# WIFI_BLE.net
KiCad netlist of a schematic drawn in Altium Designer
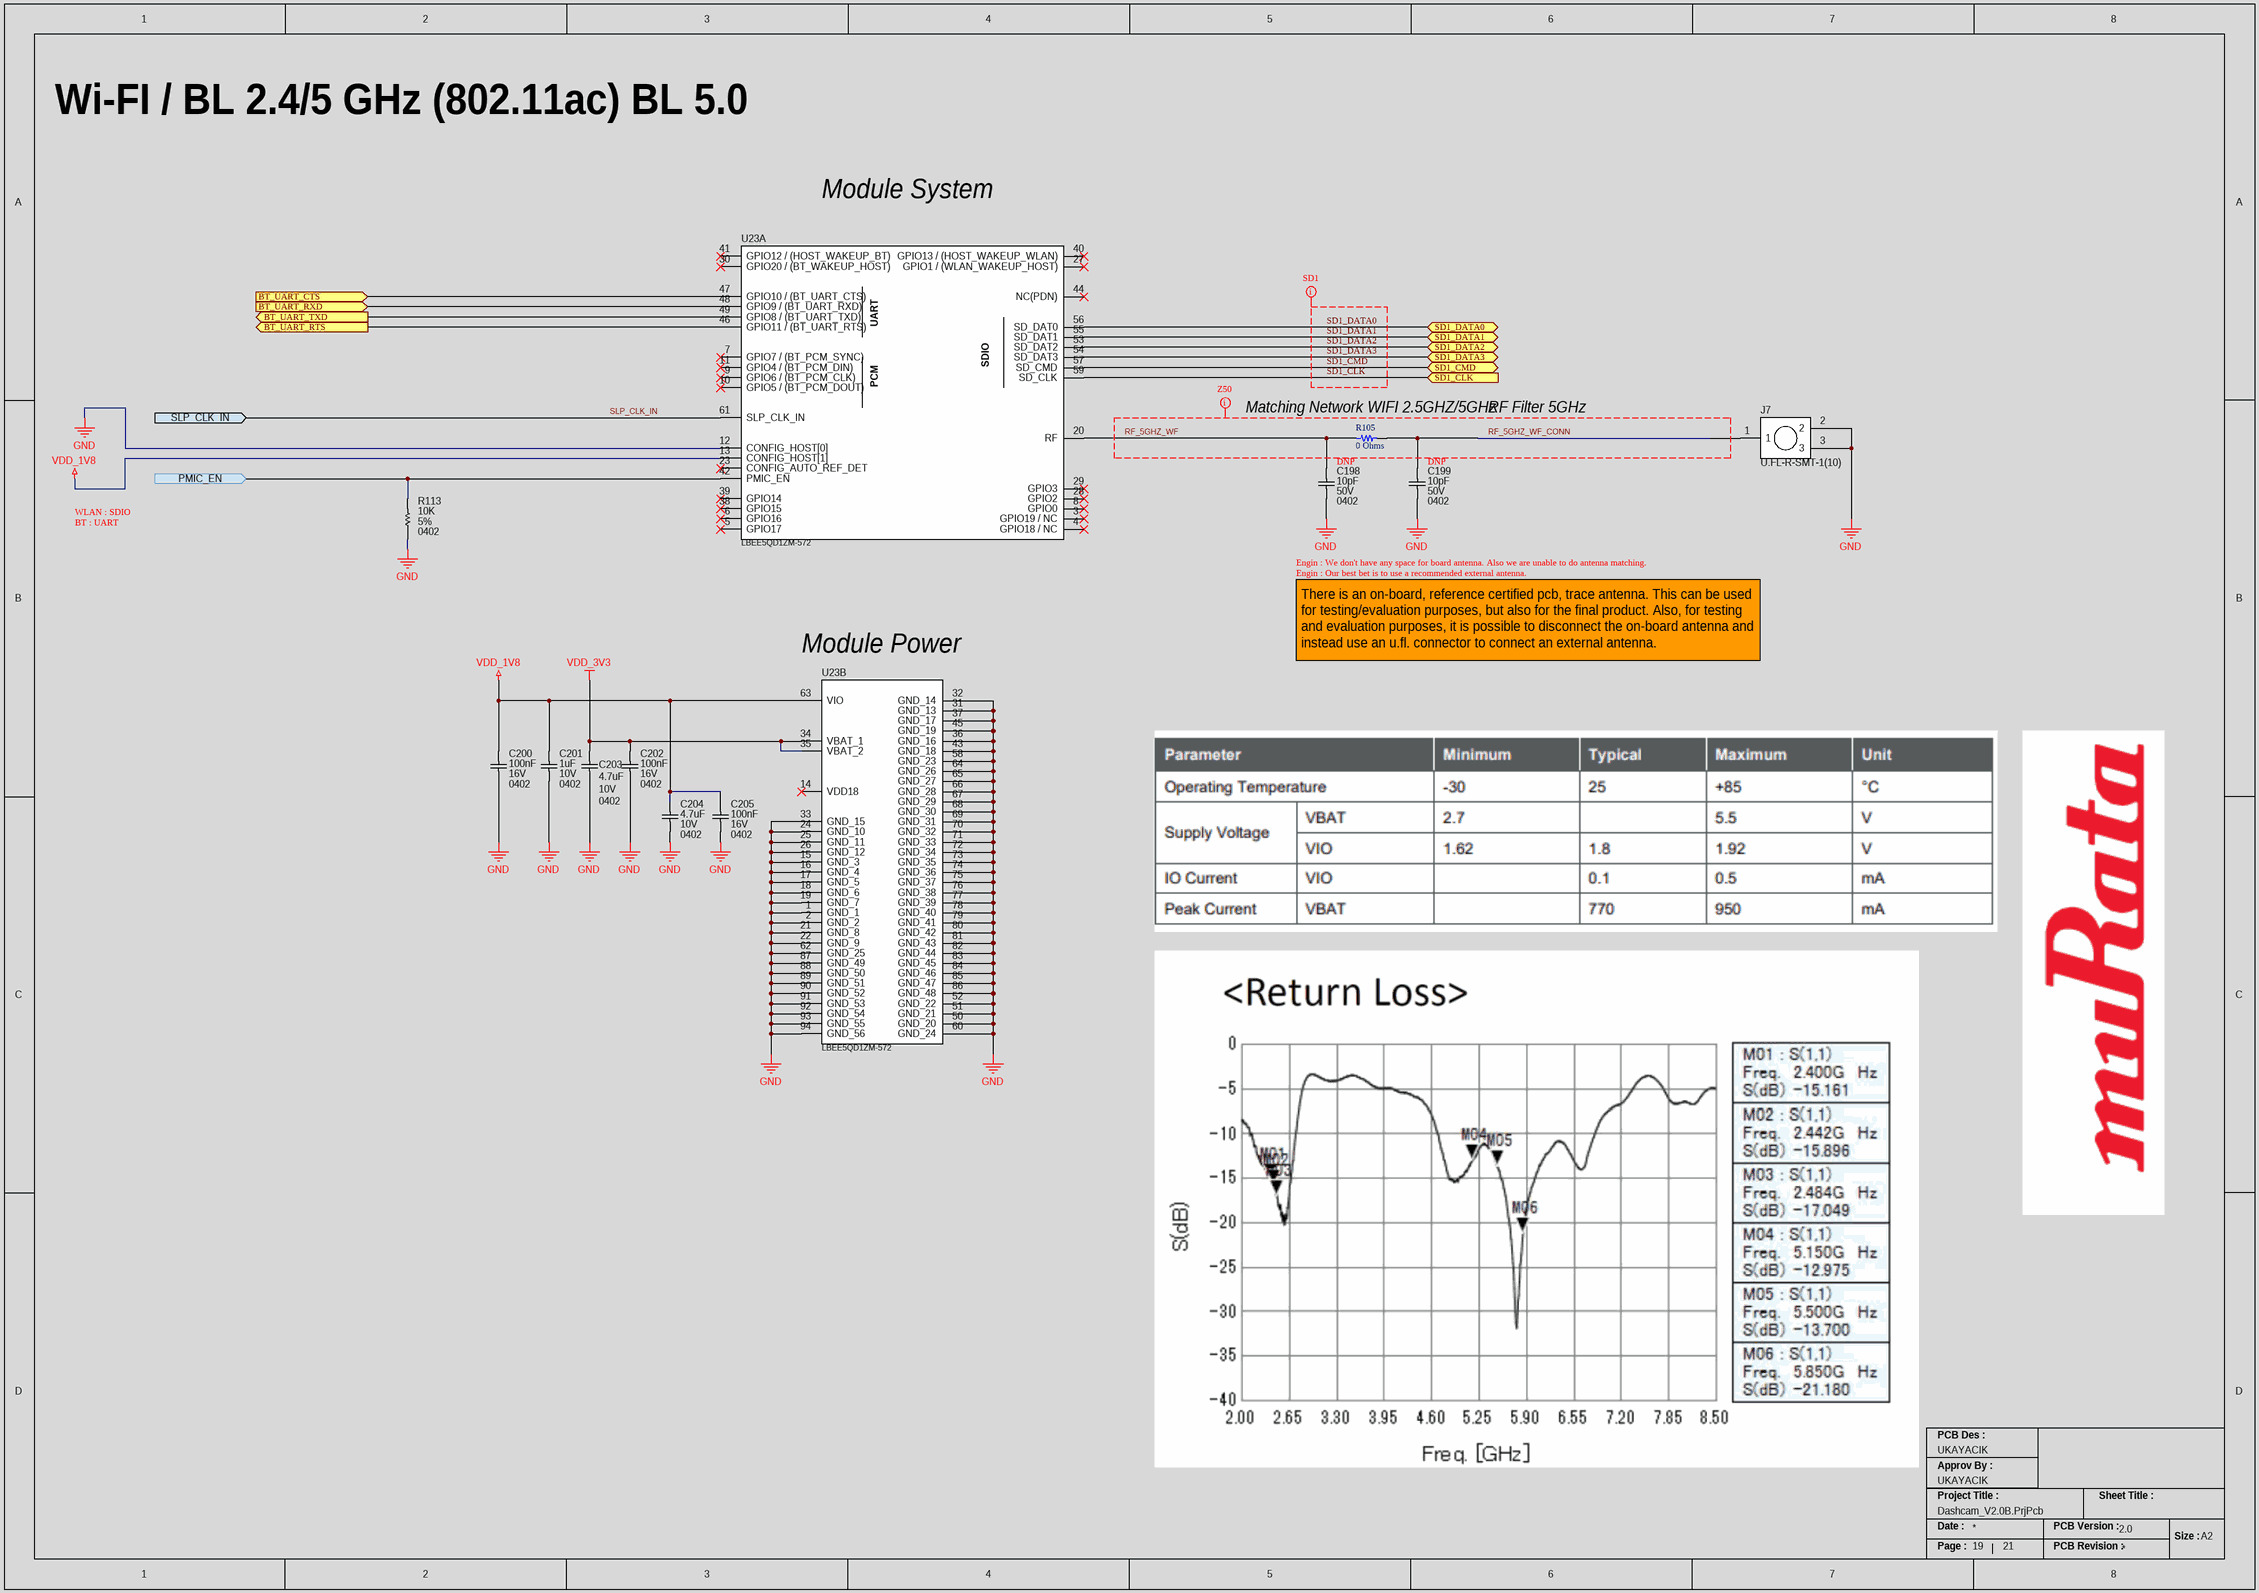
[diagram p0: WIFI_BLE.SchDoc]

(export (version "E")
  (design (tool "Eeschema 10.0.6"))
  (components
    (comp (ref "C198")
      (value "GJM1555C1H100FB01D")
      (footprint "CAP_0402_CAPC1005X05N")
      (description "Multilayer Ceramic Capacitor, 10 pF, 50 V, ± 1%, C0G (NP0), 0402 [1005 Metric]")
      (fields
        (field (name "MANUFACTURER") "Murata")
        (field (name "TOLERANCE") "1%")
        (field (name "CASE/PACKAGE") "0402")
        (field (name "VOLTAGE RATING") "50V")
        (field (name "CAPACITANCE") "10pF")
      )
      (libsource (lib "Electronic Devices_LIB") (part "CAP_10PF_50V_NP0_0402"))
    )
    (comp (ref "C199")
      (value "GJM1555C1H100FB01D")
      (footprint "CAP_0402_CAPC1005X05N")
      (description "Multilayer Ceramic Capacitor, 10 pF, 50 V, ± 1%, C0G (NP0), 0402 [1005 Metric]")
      (fields
        (field (name "MANUFACTURER") "Murata")
        (field (name "TOLERANCE") "1%")
        (field (name "CASE/PACKAGE") "0402")
        (field (name "VOLTAGE RATING") "50V")
        (field (name "CAPACITANCE") "10pF")
      )
      (libsource (lib "Electronic Devices_LIB") (part "CAP_10PF_50V_NP0_0402"))
    )
    (comp (ref "C200")
      (value "CL05B104KO5NNNC")
      (footprint "CAP_0402_CAPC1005X05N")
      (description "Multilayer Ceramic Capacitor, 0.1 uF, 16 V, ± 10%, X7R, 0402 [1005 Metric]")
      (fields
        (field (name "MANUFACTURER") "Samsung")
        (field (name "TOLERANCE") "10%")
        (field (name "VOLTAGE RATING") "16V")
        (field (name "CAPACITANCE") "100nF")
        (field (name "CASE/PACKAGE") "0402")
      )
      (libsource (lib "Electronic Devices_LIB") (part "CAP_100NF_16V_X7R_0402"))
    )
    (comp (ref "C201")
      (value "GRM155C81A105KA12D")
      (footprint "CAP_0402_CAPC1005X05N")
      (description "0402 10 V 1 uF ±10% Tolerance X6S Multilayer Ceramic Capacitor")
      (fields
        (field (name "MANUFACTURER") "Murata")
        (field (name "TOLERANCE") "10%")
        (field (name "VOLTAGE RATING") "10V")
        (field (name "CAPACITANCE") "1uF")
        (field (name "CASE/PACKAGE") "0402")
      )
      (libsource (lib "Electronic Devices_LIB") (part "CAP_1UF_10V_X6S_0402"))
    )
    (comp (ref "C202")
      (value "CL05B104KO5NNNC")
      (footprint "CAP_0402_CAPC1005X05N")
      (description "Multilayer Ceramic Capacitor, 0.1 uF, 16 V, ± 10%, X7R, 0402 [1005 Metric]")
      (fields
        (field (name "MANUFACTURER") "Samsung")
        (field (name "TOLERANCE") "10%")
        (field (name "VOLTAGE RATING") "16V")
        (field (name "CAPACITANCE") "100nF")
        (field (name "CASE/PACKAGE") "0402")
      )
      (libsource (lib "Electronic Devices_LIB") (part "CAP_100NF_16V_X7R_0402"))
    )
    (comp (ref "C203")
      (value "CL05A475KP5NRNC")
      (footprint "CAP_0402_CAPC1005X05N")
      (description "Multilayer Ceramic Capacitor, 4.7 uF, 10 V, ± 10%, X5R, 0402 [1005 Metric]")
      (fields
        (field (name "MANUFACTURER") "Samsung")
        (field (name "TOLERANCE") "10%")
        (field (name "CAPACITANCE") "4.7uF")
        (field (name "VOLTAGE RATING") "10V")
        (field (name "CASE/PACKAGE") "0402")
      )
      (libsource (lib "Electronic Devices_LIB") (part "CAP_4.7UF_10V_X5R_0402"))
    )
    (comp (ref "C204")
      (value "CL05A475KP5NRNC")
      (footprint "CAP_0402_CAPC1005X05N")
      (description "Multilayer Ceramic Capacitor, 4.7 uF, 10 V, ± 10%, X5R, 0402 [1005 Metric]")
      (fields
        (field (name "MANUFACTURER") "Samsung")
        (field (name "TOLERANCE") "10%")
        (field (name "CAPACITANCE") "4.7uF")
        (field (name "VOLTAGE RATING") "10V")
        (field (name "CASE/PACKAGE") "0402")
      )
      (libsource (lib "Electronic Devices_LIB") (part "CAP_4.7UF_10V_X5R_0402"))
    )
    (comp (ref "C205")
      (value "CL05B104KO5NNNC")
      (footprint "CAP_0402_CAPC1005X05N")
      (description "Multilayer Ceramic Capacitor, 0.1 uF, 16 V, ± 10%, X7R, 0402 [1005 Metric]")
      (fields
        (field (name "MANUFACTURER") "Samsung")
        (field (name "TOLERANCE") "10%")
        (field (name "VOLTAGE RATING") "16V")
        (field (name "CAPACITANCE") "100nF")
        (field (name "CASE/PACKAGE") "0402")
      )
      (libsource (lib "Electronic Devices_LIB") (part "CAP_100NF_16V_X7R_0402"))
    )
    (comp (ref "J7")
      (value "U.FL-R-SMT-1(10)")
      (footprint "CONN_UFL_U.FL-R-SMT-1(10)")
      (description "RF Connector, 1 Contact(s), Male, Board Mount, Surface Mount Terminal, Receptacle")
      (fields (field (name "MANUFACTURER") "Hirose"))
      (libsource (lib "Electronic Devices_LIB") (part "CONN_UFL_RF_5OR_U.FL-R-SMT-1(10)"))
    )
    (comp (ref "R105")
      (value "0 Ohms")
      (footprint "RES 0402_1005")
      (description "RES 0 OHM JUMPER 1/16W 0402")
      (fields (field (name "PART NUMBER") "RCG04020000Z0ED") (field (name "MANUFACTURER") "Vishay Dale"))
      (libsource (lib "Celestial Altium Library - altium_library") (part "Resistor"))
    )
    (comp (ref "R113")
      (value "ERJ-2GEJ103X")
      (footprint "RES_0402_RESC1005X04N")
      (description "Res Thick Film 0402 10K Ohm 5% 1/10W ±200ppm/°C Molded SMD Punched Carrier T/R")
      (fields
        (field (name "MANUFACTURER") "Panasonic")
        (field (name "TOLERANCE") "5%")
        (field (name "RESISTANCE") "10K")
        (field (name "CASE/PACKAGE") "0402")
      )
      (libsource (lib "Electronic Devices_LIB") (part "RES_10K_5%_100mW_0402"))
    )
    (comp (ref "U23")
      (value "LBEE5QD1ZM-572")
      (footprint "IC_WIFI_BLE_LBEE5QD1ZM572")
      (description "2.4 to 5.825GHz Bluetooth WiFi 802.11a/b/g/-c, Bluetooth v5.1 Transceiver Module")
      (fields (field (name "MOUSER PART NUMBER") "81-LBEE5QD1ZM-572") (field (name "MANUFACTURER") "Murata"))
      (libsource (lib "Electronic Devices_LIB") (part "IC_WIFI_BLE_LBEE5QD1ZM-572"))
    )
  )
  (nets
    (net (code "1") (name "/BT_UART_CTS") (class "Default")
      (node (ref "U23") (pin "47") (pinfunction "GPIO10_/_(BT_UART_CTS)_47") (pintype "passive"))
    )
    (net (code "2") (name "/BT_UART_RTS") (class "Default")
      (node (ref "U23") (pin "46") (pinfunction "GPIO11_/_(BT_UART_RTS)_46") (pintype "passive"))
    )
    (net (code "3") (name "/BT_UART_RXD") (class "Default")
      (node (ref "U23") (pin "48") (pinfunction "GPIO9_/_(BT_UART_RXD)_48") (pintype "passive"))
    )
    (net (code "4") (name "/BT_UART_TXD") (class "Default")
      (node (ref "U23") (pin "49") (pinfunction "GPIO8_/_(BT_UART_TXD)_49") (pintype "passive"))
    )
    (net (code "5") (name "/PMIC_EN") (class "Default")
      (node (ref "R113") (pin "2") (pinfunction "2_2") (pintype "passive"))
      (node (ref "U23") (pin "42") (pinfunction "PMIC_EN_42") (pintype "passive"))
    )
    (net (code "6") (name "/RF_5GHZ_WF") (class "Default")
      (node (ref "C198") (pin "2") (pinfunction "2_2") (pintype "passive"))
      (node (ref "R105") (pin "1") (pinfunction "1_1") (pintype "passive"))
      (node (ref "U23") (pin "20") (pinfunction "RF_20") (pintype "passive"))
    )
    (net (code "7") (name "/RF_5GHZ_WF_CONN") (class "Default")
      (node (ref "C199") (pin "2") (pinfunction "2_2") (pintype "passive"))
      (node (ref "J7") (pin "1") (pinfunction "1_1") (pintype "passive"))
      (node (ref "R105") (pin "2") (pinfunction "2_2") (pintype "passive"))
    )
    (net (code "8") (name "/SD1_CLK") (class "Default")
      (node (ref "U23") (pin "59") (pinfunction "SD_CLK_59") (pintype "passive"))
    )
    (net (code "9") (name "/SD1_CMD") (class "Default")
      (node (ref "U23") (pin "57") (pinfunction "SD_CMD_57") (pintype "passive"))
    )
    (net (code "10") (name "/SD1_DATA0") (class "Default")
      (node (ref "U23") (pin "56") (pinfunction "SD_DAT0_56") (pintype "passive"))
    )
    (net (code "11") (name "/SD1_DATA1") (class "Default")
      (node (ref "U23") (pin "55") (pinfunction "SD_DAT1_55") (pintype "passive"))
    )
    (net (code "12") (name "/SD1_DATA2") (class "Default")
      (node (ref "U23") (pin "53") (pinfunction "SD_DAT2_53") (pintype "passive"))
    )
    (net (code "13") (name "/SD1_DATA3") (class "Default")
      (node (ref "U23") (pin "54") (pinfunction "SD_DAT3_54") (pintype "passive"))
    )
    (net (code "14") (name "/SLP_CLK_IN") (class "Default")
      (node (ref "U23") (pin "61") (pinfunction "SLP_CLK_IN_61") (pintype "passive"))
    )
    (net (code "15") (name "GND") (class "Default")
      (node (ref "C198") (pin "1") (pinfunction "1_1") (pintype "passive"))
      (node (ref "C199") (pin "1") (pinfunction "1_1") (pintype "passive"))
      (node (ref "C200") (pin "1") (pinfunction "1_1") (pintype "passive"))
      (node (ref "C201") (pin "1") (pinfunction "1_1") (pintype "passive"))
      (node (ref "C202") (pin "1") (pinfunction "1_1") (pintype "passive"))
      (node (ref "C203") (pin "1") (pinfunction "1_1") (pintype "passive"))
      (node (ref "C204") (pin "1") (pinfunction "1_1") (pintype "passive"))
      (node (ref "C205") (pin "1") (pinfunction "1_1") (pintype "passive"))
      (node (ref "J7") (pin "2") (pinfunction "2_2") (pintype "passive"))
      (node (ref "J7") (pin "3") (pinfunction "3_3") (pintype "passive"))
      (node (ref "R113") (pin "1") (pinfunction "1_1") (pintype "passive"))
      (node (ref "U23") (pin "1") (pinfunction "GND_1_1") (pintype "passive"))
      (node (ref "U23") (pin "12") (pinfunction "CONFIG_HOST[0]_12") (pintype "passive"))
      (node (ref "U23") (pin "15") (pinfunction "GND_3_15") (pintype "passive"))
      (node (ref "U23") (pin "16") (pinfunction "GND_4_16") (pintype "passive"))
      (node (ref "U23") (pin "17") (pinfunction "GND_5_17") (pintype "passive"))
      (node (ref "U23") (pin "18") (pinfunction "GND_6_18") (pintype "passive"))
      (node (ref "U23") (pin "19") (pinfunction "GND_7_19") (pintype "passive"))
      (node (ref "U23") (pin "2") (pinfunction "GND_2_2") (pintype "passive"))
      (node (ref "U23") (pin "21") (pinfunction "GND_8_21") (pintype "passive"))
      (node (ref "U23") (pin "22") (pinfunction "GND_9_22") (pintype "passive"))
      (node (ref "U23") (pin "24") (pinfunction "GND_10_24") (pintype "passive"))
      (node (ref "U23") (pin "25") (pinfunction "GND_11_25") (pintype "passive"))
      (node (ref "U23") (pin "26") (pinfunction "GND_12_26") (pintype "passive"))
      (node (ref "U23") (pin "31") (pinfunction "GND_13_31") (pintype "passive"))
      (node (ref "U23") (pin "32") (pinfunction "GND_14_32") (pintype "passive"))
      (node (ref "U23") (pin "33") (pinfunction "GND_15_33") (pintype "passive"))
      (node (ref "U23") (pin "36") (pinfunction "GND_16_36") (pintype "passive"))
      (node (ref "U23") (pin "37") (pinfunction "GND_17_37") (pintype "passive"))
      (node (ref "U23") (pin "43") (pinfunction "GND_18_43") (pintype "passive"))
      (node (ref "U23") (pin "45") (pinfunction "GND_19_45") (pintype "passive"))
      (node (ref "U23") (pin "50") (pinfunction "GND_20_50") (pintype "passive"))
      (node (ref "U23") (pin "51") (pinfunction "GND_21_51") (pintype "passive"))
      (node (ref "U23") (pin "52") (pinfunction "GND_22_52") (pintype "passive"))
      (node (ref "U23") (pin "58") (pinfunction "GND_23_58") (pintype "passive"))
      (node (ref "U23") (pin "60") (pinfunction "GND_24_60") (pintype "passive"))
      (node (ref "U23") (pin "62") (pinfunction "GND_25_62") (pintype "passive"))
      (node (ref "U23") (pin "64") (pinfunction "GND_26_64") (pintype "passive"))
      (node (ref "U23") (pin "65") (pinfunction "GND_27_65") (pintype "passive"))
      (node (ref "U23") (pin "66") (pinfunction "GND_28_66") (pintype "passive"))
      (node (ref "U23") (pin "67") (pinfunction "GND_29_67") (pintype "passive"))
      (node (ref "U23") (pin "68") (pinfunction "GND_30_68") (pintype "passive"))
      (node (ref "U23") (pin "69") (pinfunction "GND_31_69") (pintype "passive"))
      (node (ref "U23") (pin "70") (pinfunction "GND_32_70") (pintype "passive"))
      (node (ref "U23") (pin "71") (pinfunction "GND_33_71") (pintype "passive"))
      (node (ref "U23") (pin "72") (pinfunction "GND_34_72") (pintype "passive"))
      (node (ref "U23") (pin "73") (pinfunction "GND_35_73") (pintype "passive"))
      (node (ref "U23") (pin "74") (pinfunction "GND_36_74") (pintype "passive"))
      (node (ref "U23") (pin "75") (pinfunction "GND_37_75") (pintype "passive"))
      (node (ref "U23") (pin "76") (pinfunction "GND_38_76") (pintype "passive"))
      (node (ref "U23") (pin "77") (pinfunction "GND_39_77") (pintype "passive"))
      (node (ref "U23") (pin "78") (pinfunction "GND_40_78") (pintype "passive"))
      (node (ref "U23") (pin "79") (pinfunction "GND_41_79") (pintype "passive"))
      (node (ref "U23") (pin "80") (pinfunction "GND_42_80") (pintype "passive"))
      (node (ref "U23") (pin "81") (pinfunction "GND_43_81") (pintype "passive"))
      (node (ref "U23") (pin "82") (pinfunction "GND_44_82") (pintype "passive"))
      (node (ref "U23") (pin "83") (pinfunction "GND_45_83") (pintype "passive"))
      (node (ref "U23") (pin "84") (pinfunction "GND_46_84") (pintype "passive"))
      (node (ref "U23") (pin "85") (pinfunction "GND_47_85") (pintype "passive"))
      (node (ref "U23") (pin "86") (pinfunction "GND_48_86") (pintype "passive"))
      (node (ref "U23") (pin "87") (pinfunction "GND_49_87") (pintype "passive"))
      (node (ref "U23") (pin "88") (pinfunction "GND_50_88") (pintype "passive"))
      (node (ref "U23") (pin "89") (pinfunction "GND_51_89") (pintype "passive"))
      (node (ref "U23") (pin "90") (pinfunction "GND_52_90") (pintype "passive"))
      (node (ref "U23") (pin "91") (pinfunction "GND_53_91") (pintype "passive"))
      (node (ref "U23") (pin "92") (pinfunction "GND_54_92") (pintype "passive"))
      (node (ref "U23") (pin "93") (pinfunction "GND_55_93") (pintype "passive"))
      (node (ref "U23") (pin "94") (pinfunction "GND_56_94") (pintype "passive"))
    )
    (net (code "16") (name "VDD_1V8") (class "Default")
      (node (ref "C200") (pin "2") (pinfunction "2_2") (pintype "passive"))
      (node (ref "C201") (pin "2") (pinfunction "2_2") (pintype "passive"))
      (node (ref "C204") (pin "2") (pinfunction "2_2") (pintype "passive"))
      (node (ref "C205") (pin "2") (pinfunction "2_2") (pintype "passive"))
      (node (ref "U23") (pin "13") (pinfunction "CONFIG_HOST[1]_13") (pintype "passive"))
      (node (ref "U23") (pin "63") (pinfunction "VIO_63") (pintype "passive"))
    )
    (net (code "17") (name "VDD_3V3") (class "Default")
      (node (ref "C202") (pin "2") (pinfunction "2_2") (pintype "passive"))
      (node (ref "C203") (pin "2") (pinfunction "2_2") (pintype "passive"))
      (node (ref "U23") (pin "34") (pinfunction "VBAT_1_34") (pintype "passive"))
      (node (ref "U23") (pin "35") (pinfunction "VBAT_2_35") (pintype "passive"))
    )
    (net (code "18") (name "unconnected-(U23A-CONFIG_AUTO_REF_DET-Pad23)") (class "Default")
      (node (ref "U23") (pin "23") (pinfunction "CONFIG_AUTO_REF_DET_23") (pintype "passive+no_connect"))
    )
    (net (code "19") (name "unconnected-(U23A-GPIO0-Pad8)") (class "Default")
      (node (ref "U23") (pin "8") (pinfunction "GPIO0_8") (pintype "passive+no_connect"))
    )
    (net (code "20") (name "unconnected-(U23A-GPIO1_{slash}_(WLAN_WAKEUP_HOST)-Pad27)") (class "Default")
      (node (ref "U23") (pin "27") (pinfunction "GPIO1_/_(WLAN_WAKEUP_HOST)_27") (pintype "passive+no_connect"))
    )
    (net (code "21") (name "unconnected-(U23A-GPIO2-Pad28)") (class "Default")
      (node (ref "U23") (pin "28") (pinfunction "GPIO2_28") (pintype "passive+no_connect"))
    )
    (net (code "22") (name "unconnected-(U23A-GPIO3-Pad29)") (class "Default")
      (node (ref "U23") (pin "29") (pinfunction "GPIO3_29") (pintype "passive+no_connect"))
    )
    (net (code "23") (name "unconnected-(U23A-GPIO4_{slash}_(BT_PCM_DIN)-Pad11)") (class "Default")
      (node (ref "U23") (pin "11") (pinfunction "GPIO4_/_(BT_PCM_DIN)_11") (pintype "passive+no_connect"))
    )
    (net (code "24") (name "unconnected-(U23A-GPIO5_{slash}_(BT_PCM_DOUT)-Pad10)") (class "Default")
      (node (ref "U23") (pin "10") (pinfunction "GPIO5_/_(BT_PCM_DOUT)_10") (pintype "passive+no_connect"))
    )
    (net (code "25") (name "unconnected-(U23A-GPIO6_{slash}_(BT_PCM_CLK)-Pad9)") (class "Default")
      (node (ref "U23") (pin "9") (pinfunction "GPIO6_/_(BT_PCM_CLK)_9") (pintype "passive+no_connect"))
    )
    (net (code "26") (name "unconnected-(U23A-GPIO7_{slash}_(BT_PCM_SYNC)-Pad7)") (class "Default")
      (node (ref "U23") (pin "7") (pinfunction "GPIO7_/_(BT_PCM_SYNC)_7") (pintype "passive+no_connect"))
    )
    (net (code "27") (name "unconnected-(U23A-GPIO12_{slash}_(HOST_WAKEUP_BT)-Pad41)") (class "Default")
      (node (ref "U23") (pin "41") (pinfunction "GPIO12_/_(HOST_WAKEUP_BT)_41") (pintype "passive+no_connect"))
    )
    (net (code "28") (name "unconnected-(U23A-GPIO13_{slash}_(HOST_WAKEUP_WLAN)-Pad40)") (class "Default")
      (node (ref "U23") (pin "40") (pinfunction "GPIO13_/_(HOST_WAKEUP_WLAN)_40") (pintype "passive+no_connect"))
    )
    (net (code "29") (name "unconnected-(U23A-GPIO14-Pad39)") (class "Default")
      (node (ref "U23") (pin "39") (pinfunction "GPIO14_39") (pintype "passive+no_connect"))
    )
    (net (code "30") (name "unconnected-(U23A-GPIO15-Pad38)") (class "Default")
      (node (ref "U23") (pin "38") (pinfunction "GPIO15_38") (pintype "passive+no_connect"))
    )
    (net (code "31") (name "unconnected-(U23A-GPIO16-Pad6)") (class "Default")
      (node (ref "U23") (pin "6") (pinfunction "GPIO16_6") (pintype "passive+no_connect"))
    )
    (net (code "32") (name "unconnected-(U23A-GPIO17-Pad5)") (class "Default")
      (node (ref "U23") (pin "5") (pinfunction "GPIO17_5") (pintype "passive+no_connect"))
    )
    (net (code "33") (name "unconnected-(U23A-GPIO18_{slash}_NC-Pad4)") (class "Default")
      (node (ref "U23") (pin "4") (pinfunction "GPIO18_/_NC_4") (pintype "passive+no_connect"))
    )
    (net (code "34") (name "unconnected-(U23A-GPIO19_{slash}_NC-Pad3)") (class "Default")
      (node (ref "U23") (pin "3") (pinfunction "GPIO19_/_NC_3") (pintype "passive+no_connect"))
    )
    (net (code "35") (name "unconnected-(U23A-GPIO20_{slash}_(BT_WAKEUP_HOST)-Pad30)") (class "Default")
      (node (ref "U23") (pin "30") (pinfunction "GPIO20_/_(BT_WAKEUP_HOST)_30") (pintype "passive+no_connect"))
    )
    (net (code "36") (name "unconnected-(U23A-NC(PDN)-Pad44)") (class "Default")
      (node (ref "U23") (pin "44") (pinfunction "NC(PDN)_44") (pintype "passive+no_connect"))
    )
    (net (code "37") (name "unconnected-(U23B-VDD18-Pad14)") (class "Default")
      (node (ref "U23") (pin "14") (pinfunction "VDD18_14") (pintype "passive+no_connect"))
    )
  )
)
